# Master_G2553.net
KiCad netlist of a schematic drawn in EAGLE
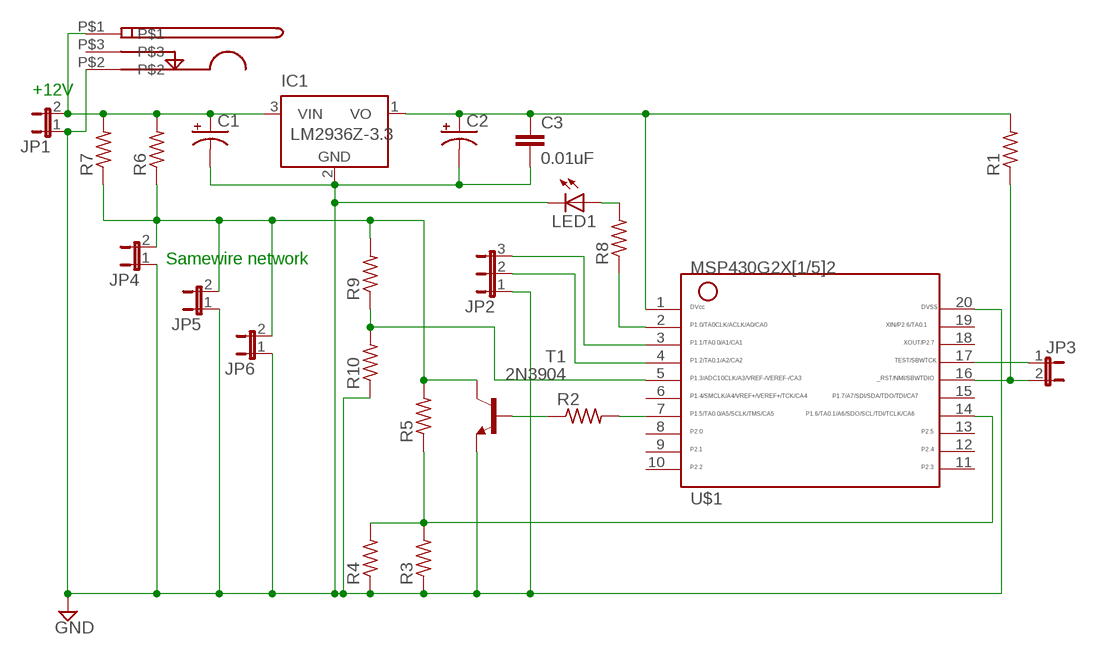
[diagram p0: schematic, sheet 1]

(export (version "E")
  (design (tool "Eeschema 10.0.6"))
  (components
    (comp (ref "C1")
      (value "CPOL-USE2.5-6")
      (footprint "eagle-import:E2,5-6")
      (libsource (lib "eagle-import") (part "CPOL-USE2.5-6"))
    )
    (comp (ref "C2")
      (value "CPOL-USE2.5-6")
      (footprint "eagle-import:E2,5-6")
      (libsource (lib "eagle-import") (part "CPOL-USE2.5-6"))
    )
    (comp (ref "C3")
      (value "0.01uF")
      (footprint "eagle-import:C7.5B3")
      (libsource (lib "eagle-import") (part "C7.5/3"))
    )
    (comp (ref "IC1")
      (value "LM2936Z-3.3")
      (footprint "eagle-import:TO92")
      (fields (field (name "MF") "NATIONAL SEMICONDUCTOR") (field (name "MPN") "LM2936Z-3.3/NOPB"))
      (libsource (lib "eagle-import") (part "LM2936?Z-3.3"))
    )
    (comp (ref "JP1")
      (value "JP1E")
      (footprint "eagle-import:JP1")
      (libsource (lib "eagle-import") (part "JP1E"))
    )
    (comp (ref "JP2")
      (value "JP2E")
      (footprint "eagle-import:JP2")
      (libsource (lib "eagle-import") (part "JP2E"))
    )
    (comp (ref "JP3")
      (value "JP1E")
      (footprint "eagle-import:JP1")
      (libsource (lib "eagle-import") (part "JP1E"))
    )
    (comp (ref "JP4")
      (value "JP1E")
      (footprint "eagle-import:JP1")
      (libsource (lib "eagle-import") (part "JP1E"))
    )
    (comp (ref "JP5")
      (value "JP1E")
      (footprint "eagle-import:JP1")
      (libsource (lib "eagle-import") (part "JP1E"))
    )
    (comp (ref "JP6")
      (value "JP1E")
      (footprint "eagle-import:JP1")
      (libsource (lib "eagle-import") (part "JP1E"))
    )
    (comp (ref "LED1")
      (value "LED3MM")
      (footprint "eagle-import:LED3MM")
      (libsource (lib "eagle-import") (part "LED3MM"))
    )
    (comp (ref "R1")
      (value "R-US_0204/2V")
      (footprint "eagle-import:0204V")
      (libsource (lib "eagle-import") (part "R-US_0204/2V"))
    )
    (comp (ref "R2")
      (value "R-US_0204/2V")
      (footprint "eagle-import:0204V")
      (libsource (lib "eagle-import") (part "R-US_0204/2V"))
    )
    (comp (ref "R3")
      (value "R-US_0204/2V")
      (footprint "eagle-import:0204V")
      (libsource (lib "eagle-import") (part "R-US_0204/2V"))
    )
    (comp (ref "R4")
      (value "R-US_0204/2V")
      (footprint "eagle-import:0204V")
      (libsource (lib "eagle-import") (part "R-US_0204/2V"))
    )
    (comp (ref "R5")
      (value "R-US_0204/2V")
      (footprint "eagle-import:0204V")
      (libsource (lib "eagle-import") (part "R-US_0204/2V"))
    )
    (comp (ref "R6")
      (value "R-US_0204/2V")
      (footprint "eagle-import:0204V")
      (libsource (lib "eagle-import") (part "R-US_0204/2V"))
    )
    (comp (ref "R7")
      (value "R-US_0204/2V")
      (footprint "eagle-import:0204V")
      (libsource (lib "eagle-import") (part "R-US_0204/2V"))
    )
    (comp (ref "R8")
      (value "R-US_0204/2V")
      (footprint "eagle-import:0204V")
      (libsource (lib "eagle-import") (part "R-US_0204/2V"))
    )
    (comp (ref "R9")
      (value "R-US_0204/2V")
      (footprint "eagle-import:0204V")
      (libsource (lib "eagle-import") (part "R-US_0204/2V"))
    )
    (comp (ref "R10")
      (value "R-US_0204/2V")
      (footprint "eagle-import:0204V")
      (libsource (lib "eagle-import") (part "R-US_0204/2V"))
    )
    (comp (ref "T1")
      (value "2N3904")
      (footprint "eagle-import:TO92")
      (libsource (lib "eagle-import") (part "2N3904"))
    )
    (comp (ref "U$1")
      (value "G2X[1/5]2---N20")
      (footprint "eagle-import:N20")
      (libsource (lib "eagle-import") (part "G2X[1/5]2---N20"))
    )
    (comp (ref "U$2")
      (value "2.1MM_5.5MM")
      (footprint "eagle-import:2.1MM_5.5MM")
      (libsource (lib "eagle-import") (part "2.1MM_5.5MM"))
    )
  )
  (nets
    (net (code "1") (name "GND") (class "Default")
      (node (ref "C1") (pin "-") (pinfunction "-_-") (pintype "passive"))
      (node (ref "C2") (pin "-") (pinfunction "-_-") (pintype "passive"))
      (node (ref "C3") (pin "2") (pinfunction "2_2") (pintype "passive"))
      (node (ref "IC1") (pin "2") (pinfunction "GND_2") (pintype "passive"))
      (node (ref "JP1") (pin "1") (pinfunction "1_1") (pintype "passive"))
      (node (ref "JP2") (pin "1") (pinfunction "1_1") (pintype "passive"))
      (node (ref "JP4") (pin "1") (pinfunction "1_1") (pintype "passive"))
      (node (ref "JP5") (pin "1") (pinfunction "1_1") (pintype "passive"))
      (node (ref "JP6") (pin "1") (pinfunction "1_1") (pintype "passive"))
      (node (ref "LED1") (pin "K") (pinfunction "C_K") (pintype "passive"))
      (node (ref "R10") (pin "1") (pinfunction "1_1") (pintype "passive"))
      (node (ref "R3") (pin "1") (pinfunction "1_1") (pintype "passive"))
      (node (ref "R4") (pin "1") (pinfunction "1_1") (pintype "passive"))
      (node (ref "T1") (pin "3") (pinfunction "E_3") (pintype "passive"))
      (node (ref "U$1") (pin "20") (pinfunction "20_20") (pintype "bidirectional"))
      (node (ref "U$2") (pin "P$2") (pinfunction "P$2_P$2") (pintype "bidirectional"))
    )
    (net (code "2") (name "Net-(IC1-VIN)") (class "Default")
      (node (ref "C1") (pin "+") (pinfunction "+_+") (pintype "passive"))
      (node (ref "IC1") (pin "3") (pinfunction "VIN_3") (pintype "input"))
      (node (ref "JP1") (pin "2") (pinfunction "2_2") (pintype "passive"))
      (node (ref "R6") (pin "2") (pinfunction "2_2") (pintype "passive"))
      (node (ref "R7") (pin "2") (pinfunction "2_2") (pintype "passive"))
      (node (ref "U$2") (pin "P$1") (pinfunction "P$1_P$1") (pintype "bidirectional"))
    )
    (net (code "3") (name "Net-(IC1-VO)") (class "Default")
      (node (ref "C2") (pin "+") (pinfunction "+_+") (pintype "passive"))
      (node (ref "C3") (pin "1") (pinfunction "1_1") (pintype "passive"))
      (node (ref "IC1") (pin "1") (pinfunction "VO_1") (pintype "passive"))
      (node (ref "R1") (pin "2") (pinfunction "2_2") (pintype "passive"))
      (node (ref "U$1") (pin "1") (pinfunction "1_1") (pintype "bidirectional"))
    )
    (net (code "4") (name "Net-(JP2-Pad2)") (class "Default")
      (node (ref "JP2") (pin "2") (pinfunction "2_2") (pintype "passive"))
      (node (ref "U$1") (pin "4") (pinfunction "4_4") (pintype "bidirectional"))
    )
    (net (code "5") (name "Net-(JP2-Pad3)") (class "Default")
      (node (ref "JP2") (pin "3") (pinfunction "3_3") (pintype "passive"))
      (node (ref "U$1") (pin "3") (pinfunction "3_3") (pintype "bidirectional"))
    )
    (net (code "6") (name "Net-(JP3-Pad1)") (class "Default")
      (node (ref "JP3") (pin "1") (pinfunction "1_1") (pintype "passive"))
      (node (ref "U$1") (pin "17") (pinfunction "17_17") (pintype "bidirectional"))
    )
    (net (code "7") (name "Net-(JP3-Pad2)") (class "Default")
      (node (ref "JP3") (pin "2") (pinfunction "2_2") (pintype "passive"))
      (node (ref "R1") (pin "1") (pinfunction "1_1") (pintype "passive"))
      (node (ref "U$1") (pin "16") (pinfunction "16_16") (pintype "bidirectional"))
    )
    (net (code "8") (name "Net-(LED1-PadA)") (class "Default")
      (node (ref "LED1") (pin "A") (pinfunction "A_A") (pintype "passive"))
      (node (ref "R8") (pin "2") (pinfunction "2_2") (pintype "passive"))
    )
    (net (code "9") (name "Net-(R2-Pad2)") (class "Default")
      (node (ref "R2") (pin "2") (pinfunction "2_2") (pintype "passive"))
      (node (ref "U$1") (pin "7") (pinfunction "7_7") (pintype "bidirectional"))
    )
    (net (code "10") (name "Net-(R3-Pad2)") (class "Default")
      (node (ref "R3") (pin "2") (pinfunction "2_2") (pintype "passive"))
      (node (ref "R4") (pin "2") (pinfunction "2_2") (pintype "passive"))
      (node (ref "R5") (pin "1") (pinfunction "1_1") (pintype "passive"))
      (node (ref "U$1") (pin "14") (pinfunction "14_14") (pintype "bidirectional"))
    )
    (net (code "11") (name "Net-(R8-Pad1)") (class "Default")
      (node (ref "R8") (pin "1") (pinfunction "1_1") (pintype "passive"))
      (node (ref "U$1") (pin "2") (pinfunction "2_2") (pintype "bidirectional"))
    )
    (net (code "12") (name "Net-(R10-Pad2)") (class "Default")
      (node (ref "R10") (pin "2") (pinfunction "2_2") (pintype "passive"))
      (node (ref "R9") (pin "1") (pinfunction "1_1") (pintype "passive"))
      (node (ref "U$1") (pin "5") (pinfunction "5_5") (pintype "bidirectional"))
    )
    (net (code "13") (name "Net-(T1-B)") (class "Default")
      (node (ref "R2") (pin "1") (pinfunction "1_1") (pintype "passive"))
      (node (ref "T1") (pin "2") (pinfunction "B_2") (pintype "passive"))
    )
    (net (code "14") (name "Net-(T1-C)") (class "Default")
      (node (ref "JP4") (pin "2") (pinfunction "2_2") (pintype "passive"))
      (node (ref "JP5") (pin "2") (pinfunction "2_2") (pintype "passive"))
      (node (ref "JP6") (pin "2") (pinfunction "2_2") (pintype "passive"))
      (node (ref "R5") (pin "2") (pinfunction "2_2") (pintype "passive"))
      (node (ref "R6") (pin "1") (pinfunction "1_1") (pintype "passive"))
      (node (ref "R7") (pin "1") (pinfunction "1_1") (pintype "passive"))
      (node (ref "R9") (pin "2") (pinfunction "2_2") (pintype "passive"))
      (node (ref "T1") (pin "1") (pinfunction "C_1") (pintype "passive"))
    )
    (net (code "15") (name "unconnected-(U$1-Pad6)") (class "Default")
      (node (ref "U$1") (pin "6") (pinfunction "6_6") (pintype "bidirectional"))
    )
    (net (code "16") (name "unconnected-(U$1-Pad8)") (class "Default")
      (node (ref "U$1") (pin "8") (pinfunction "8_8") (pintype "bidirectional"))
    )
    (net (code "17") (name "unconnected-(U$1-Pad9)") (class "Default")
      (node (ref "U$1") (pin "9") (pinfunction "9_9") (pintype "bidirectional"))
    )
    (net (code "18") (name "unconnected-(U$1-Pad10)") (class "Default")
      (node (ref "U$1") (pin "10") (pinfunction "10_10") (pintype "bidirectional"))
    )
    (net (code "19") (name "unconnected-(U$1-Pad11)") (class "Default")
      (node (ref "U$1") (pin "11") (pinfunction "11_11") (pintype "bidirectional"))
    )
    (net (code "20") (name "unconnected-(U$1-Pad12)") (class "Default")
      (node (ref "U$1") (pin "12") (pinfunction "12_12") (pintype "bidirectional"))
    )
    (net (code "21") (name "unconnected-(U$1-Pad13)") (class "Default")
      (node (ref "U$1") (pin "13") (pinfunction "13_13") (pintype "bidirectional"))
    )
    (net (code "22") (name "unconnected-(U$1-Pad15)") (class "Default")
      (node (ref "U$1") (pin "15") (pinfunction "15_15") (pintype "bidirectional"))
    )
    (net (code "23") (name "unconnected-(U$1-Pad18)") (class "Default")
      (node (ref "U$1") (pin "18") (pinfunction "18_18") (pintype "bidirectional"))
    )
    (net (code "24") (name "unconnected-(U$1-Pad19)") (class "Default")
      (node (ref "U$1") (pin "19") (pinfunction "19_19") (pintype "bidirectional"))
    )
    (net (code "25") (name "unconnected-(U$2-PadP$3)") (class "Default")
      (node (ref "U$2") (pin "P$3") (pinfunction "P$3_P$3") (pintype "bidirectional"))
    )
  )
)
